# Thunder-Refix.net
KiCad netlist of a schematic drawn in Altium Designer
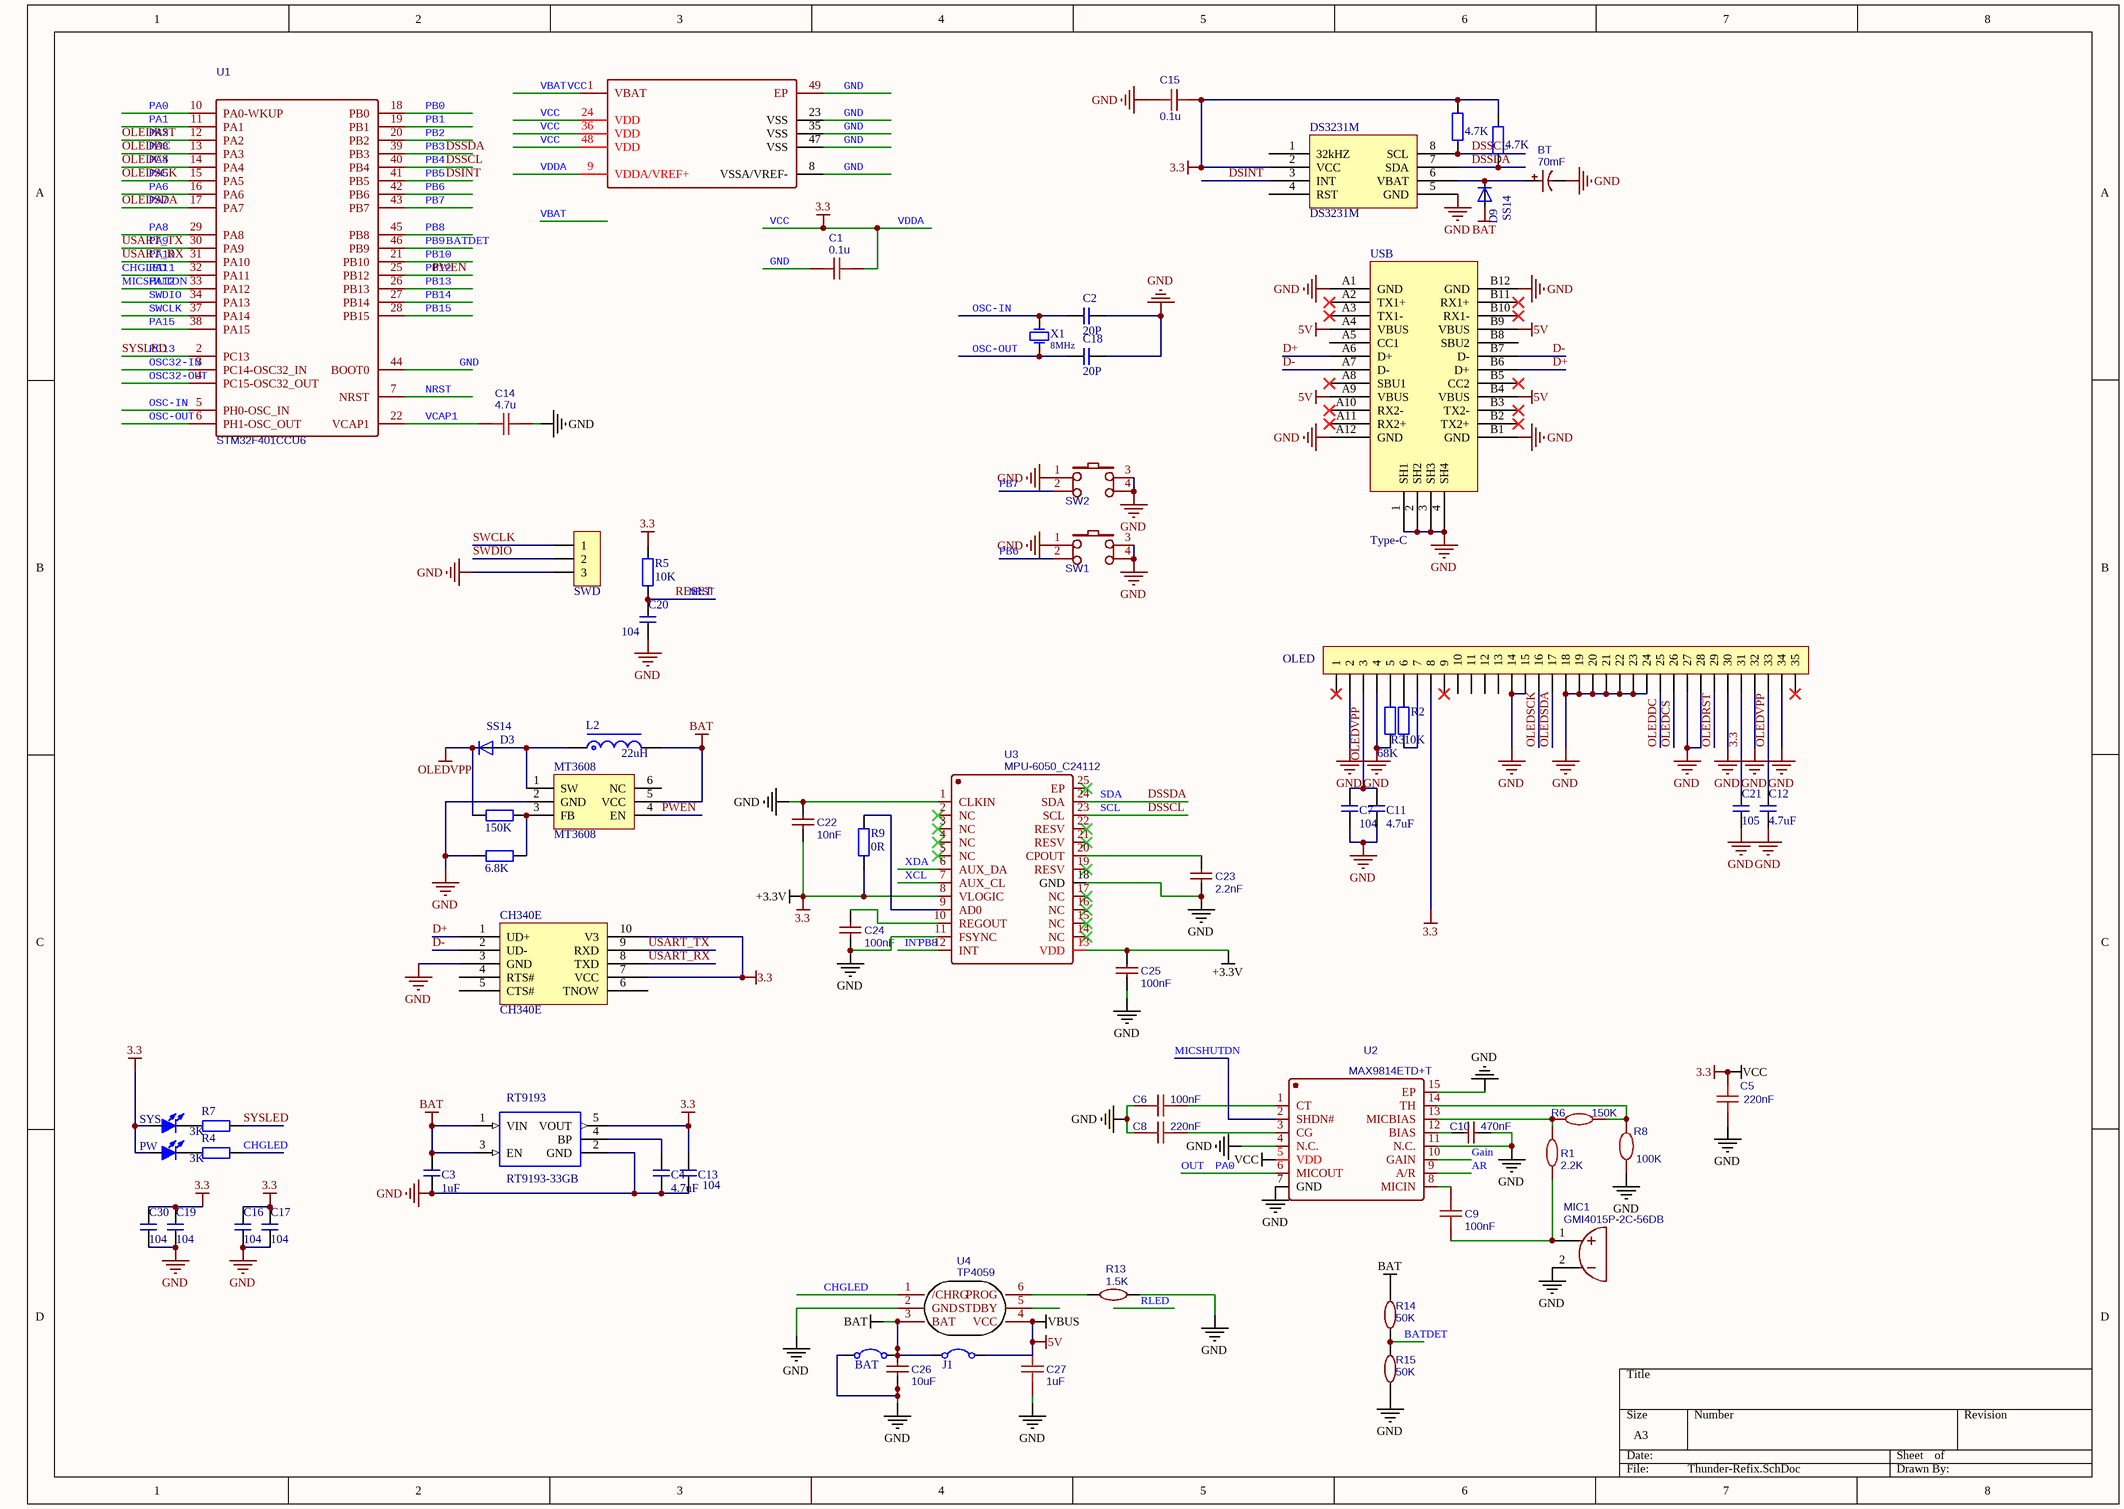
[diagram p0: Thunder-Refix.SchDoc]

(export (version "E")
  (design (tool "Eeschema 10.0.6"))
  (components
    (comp (ref "BAT")
      (value "Jump")
      (footprint "jump1")
      (description "跳线")
      (fields (field (name "版权归属") "源创客"))
      (libsource (lib "3.2   - 跳线") (part "Jump"))
    )
    (comp (ref "BT")
      (value "70mF")
      (footprint "MS621FE-FL11E")
      (fields
        (field (name "BOM_SUPPLIER PART") "C132600")
        (field (name "BOM_MANUFACTURER PART") "SM3R3703T01")
        (field (name "CONTRIBUTOR") "LCSC")
      )
      (libsource (lib "altium-import") (part "root_0_70mF_"))
    )
    (comp (ref "C1")
      (value "0.1u")
      (footprint "0603C")
      (fields (field (name "CONTRIBUTOR") "LCEDA_Lib"))
      (libsource (lib "altium-import") (part "root_2_0.1u_"))
    )
    (comp (ref "C2") (value "20P") (footprint "0603C") (libsource (lib "Schlib1") (part "电容")))
    (comp (ref "C3") (value "1uF") (footprint "0603C") (libsource (lib "Schlib1") (part "电容")))
    (comp (ref "C4") (value "4.7uF") (footprint "0603C") (libsource (lib "Schlib1") (part "电容")))
    (comp (ref "C5")
      (value "220nF")
      (footprint "0603c")
      (fields
        (field (name "BOM_SUPPLIER PART") "C354366")
        (field (name "BOM_MANUFACTURER PART") "GCJ21BR71H224KA01L")
        (field (name "CONTRIBUTOR") "LCSC")
      )
      (libsource (lib "altium-import") (part "root_1_220nF_"))
    )
    (comp (ref "C6")
      (value "100nF")
      (footprint "0603c")
      (fields
        (field (name "BOM_SUPPLIER PART") "C444732")
        (field (name "BOM_MANUFACTURER PART") "FS055C104K4Z2A")
        (field (name "CONTRIBUTOR") "LCSC")
      )
      (libsource (lib "") (part "root_1_100nF__1"))
    )
    (comp (ref "C7") (value "104") (footprint "0603C") (libsource (lib "Schlib1") (part "电容")))
    (comp (ref "C8")
      (value "220nF")
      (footprint "0603c")
      (fields
        (field (name "BOM_SUPPLIER PART") "C354366")
        (field (name "BOM_MANUFACTURER PART") "GCJ21BR71H224KA01L")
        (field (name "CONTRIBUTOR") "LCSC")
      )
      (libsource (lib "altium-import") (part "root_0_220nF_"))
    )
    (comp (ref "C9")
      (value "100nF")
      (footprint "0603c")
      (fields
        (field (name "BOM_SUPPLIER PART") "C444732")
        (field (name "BOM_MANUFACTURER PART") "FS055C104K4Z2A")
        (field (name "CONTRIBUTOR") "LCSC")
      )
      (libsource (lib "altium-import") (part "root_0_100nF_"))
    )
    (comp (ref "C10")
      (value "470nF")
      (footprint "0603c")
      (fields
        (field (name "BOM_MANUFACTURER PART") "CL21B474KBFNNNE")
        (field (name "BOM_SUPPLIER PART") "C13967")
      )
      (libsource (lib "altium-import") (part "root_0_470nF_"))
    )
    (comp (ref "C11") (value "4.7uF") (footprint "0603C") (libsource (lib "Schlib1") (part "电容")))
    (comp (ref "C12") (value "4.7uF") (footprint "0603C") (libsource (lib "Schlib1") (part "电容")))
    (comp (ref "C13") (value "104") (footprint "0603C") (libsource (lib "Schlib1") (part "电容")))
    (comp (ref "C14")
      (value "4.7u")
      (footprint "0603C")
      (fields (field (name "CONTRIBUTOR") "LCEDA_Lib"))
      (libsource (lib "altium-import") (part "root_0_4.7u_"))
    )
    (comp (ref "C15")
      (value "0.1u")
      (footprint "0603C")
      (fields (field (name "CONTRIBUTOR") "LCEDA_Lib"))
      (libsource (lib "altium-import") (part "root_2_0.1u_"))
    )
    (comp (ref "C16") (value "104") (footprint "0603C") (libsource (lib "Schlib1") (part "电容")))
    (comp (ref "C17") (value "104") (footprint "0603C") (libsource (lib "Schlib1") (part "电容")))
    (comp (ref "C18") (value "20P") (footprint "0603C") (libsource (lib "Schlib1") (part "电容")))
    (comp (ref "C19") (value "104") (footprint "0603C") (libsource (lib "Schlib1") (part "电容")))
    (comp (ref "C20") (value "104") (footprint "0603C") (libsource (lib "Schlib1") (part "电容")))
    (comp (ref "C21") (value "105") (footprint "0603C") (libsource (lib "Schlib1") (part "电容")))
    (comp (ref "C22")
      (value "10nF")
      (footprint "0603C")
      (fields
        (field (name "BOM_MANUFACTURER PART") "0603B103K500NT")
        (field (name "BOM_SUPPLIER PART") "C57112")
      )
      (libsource (lib "altium-import") (part "root_1_10nF_"))
    )
    (comp (ref "C23")
      (value "2.2nF")
      (footprint "0603C")
      (fields
        (field (name "BOM_MANUFACTURER PART") "0603B222K500NT")
        (field (name "BOM_SUPPLIER PART") "C1604")
      )
      (libsource (lib "altium-import") (part "root_1_2.2nF_"))
    )
    (comp (ref "C24")
      (value "100nF")
      (footprint "0603C")
      (fields
        (field (name "BOM_MANUFACTURER PART") "CL05B104KO5NNNC")
        (field (name "BOM_SUPPLIER PART") "C1525")
      )
      (libsource (lib "altium-import") (part "root_1_100nF_"))
    )
    (comp (ref "C25")
      (value "100nF")
      (footprint "0603C")
      (fields
        (field (name "BOM_MANUFACTURER PART") "CL05B104KO5NNNC")
        (field (name "BOM_SUPPLIER PART") "C1525")
      )
      (libsource (lib "altium-import") (part "root_1_100nF_"))
    )
    (comp (ref "C26")
      (value "10uF")
      (footprint "0603c")
      (fields
        (field (name "BOM_SUPPLIER PART") "C162317")
        (field (name "BOM_MANUFACTURER PART") "GRM21BB31C106KE15L")
        (field (name "CONTRIBUTOR") "LCSC")
      )
      (libsource (lib "altium-import") (part "root_1_10uF_"))
    )
    (comp (ref "C27")
      (value "1uF")
      (footprint "0603c")
      (fields
        (field (name "BOM_SUPPLIER PART") "C319195")
        (field (name "BOM_MANUFACTURER PART") "UMK212BJ105KG-T")
        (field (name "CONTRIBUTOR") "LCSC")
      )
      (libsource (lib "altium-import") (part "root_1_1uF_"))
    )
    (comp (ref "C30") (value "104") (footprint "0603C") (libsource (lib "Schlib1") (part "电容")))
    (comp (ref "CH340E") (value "CH340E") (footprint "MSOP10_L") (libsource (lib "CUBE_T1") (part "CH340E")))
    (comp (ref "D3")
      (value "SS14")
      (footprint "SOD323_1N4148WS")
      (description "Diode Switching 75V 0.3A 2-Pin SOD-323 T/R")
      (fields (field (name "MF") "ON Semiconductor") (field (name "MP") "1N4148WS"))
      (libsource (lib "1N4148WS") (part "1N4148WS"))
    )
    (comp (ref "D9")
      (value "SS14")
      (footprint "SOD323_1N4148WS")
      (description "Diode Switching 75V 0.3A 2-Pin SOD-323 T/R")
      (fields (field (name "MF") "ON Semiconductor") (field (name "MP") "1N4148WS"))
      (libsource (lib "1N4148WS") (part "1N4148WS"))
    )
    (comp (ref "DS3231M") (value "DS3231M") (footprint "SOP8") (libsource (lib "CUBE_T1") (part "DS3231M")))
    (comp (ref "J1")
      (value "Jump")
      (footprint "jump1")
      (description "跳线")
      (fields (field (name "版权归属") "源创客"))
      (libsource (lib "3.2   - 跳线") (part "Jump"))
    )
    (comp (ref "L2")
      (value "22uH")
      (footprint "1210-ec")
      (description "功率屏蔽电感")
      (fields (field (name "版权归属") "源创客"))
      (libsource (lib "3.1   - 电阻-电容-电感") (part "L-CDRH"))
    )
    (comp (ref "MIC1")
      (value "GMI4015P-2C-56DB")
      (footprint "MIC-TH_BD4.0-P2.00-D0.4-L-FD")
      (fields
        (field (name "BOM_SUPPLIER PART") "C233299")
        (field (name "BOM_MANUFACTURER PART") "GMI4015P-2C-56db")
        (field (name "CONTRIBUTOR") "LCSC")
      )
      (libsource (lib "altium-import") (part "root_0_GMI4015P-2C-56DB_"))
    )
    (comp (ref "MT3608")
      (value "MT3608")
      (footprint "SOT23-6N")
      (description "可调升压芯片")
      (fields (field (name "版权归属") "源创客"))
      (libsource (lib "1.3   - 电源类芯片") (part "SX1308"))
    )
    (comp (ref "OLED")
      (value "FPC1.0-35P")
      (footprint "1.69 OLED")
      (description "FPC连接器")
      (fields (field (name "版权归属") "源创客"))
      (libsource (lib "4.14 - FPC连接器") (part "FPC-35P"))
    )
    (comp (ref "PW")
      (value "白色")
      (footprint "0603LED")
      (description "方形LED")
      (fields (field (name "版权归属") "源创客"))
      (libsource (lib "9.1   - LED") (part "LED-F234"))
    )
    (comp (ref "R1")
      (value "2.2K")
      (footprint "0603r")
      (fields
        (field (name "BOM_SUPPLIER PART") "C325769")
        (field (name "BOM_MANUFACTURER PART") "RMC08052.2K1%N")
        (field (name "CONTRIBUTOR") "LCSC")
      )
      (libsource (lib "altium-import") (part "root_1_2.2K_"))
    )
    (comp (ref "R2")
      (value "10K")
      (footprint "0603R")
      (description "贴片电阻")
      (fields (field (name "版权归属") "源创客"))
      (libsource (lib "3.1   - 电阻-电容-电感") (part "R"))
    )
    (comp (ref "R3")
      (value "68K")
      (footprint "0603R")
      (description "贴片电阻")
      (fields (field (name "版权归属") "源创客"))
      (libsource (lib "3.1   - 电阻-电容-电感") (part "R"))
    )
    (comp (ref "R4")
      (value "3K")
      (footprint "0603R")
      (description "贴片电阻")
      (fields (field (name "版权归属") "源创客"))
      (libsource (lib "3.1   - 电阻-电容-电感") (part "R"))
    )
    (comp (ref "R5")
      (value "10K")
      (footprint "0603R")
      (description "贴片电阻")
      (fields (field (name "版权归属") "源创客"))
      (libsource (lib "3.1   - 电阻-电容-电感") (part "R"))
    )
    (comp (ref "R6")
      (value "150K")
      (footprint "0603r")
      (fields
        (field (name "BOM_SUPPLIER PART") "C325765")
        (field (name "BOM_MANUFACTURER PART") "RMC0805150K1%N")
        (field (name "CONTRIBUTOR") "LCSC")
      )
      (libsource (lib "altium-import") (part "root_0_150K_"))
    )
    (comp (ref "R7")
      (value "3K")
      (footprint "0603R")
      (description "贴片电阻")
      (fields (field (name "版权归属") "源创客"))
      (libsource (lib "3.1   - 电阻-电容-电感") (part "R"))
    )
    (comp (ref "R8")
      (value "100K")
      (footprint "0603r")
      (fields
        (field (name "BOM_SUPPLIER PART") "C346756")
        (field (name "BOM_MANUFACTURER PART") "RTAN0805BKE100K")
        (field (name "CONTRIBUTOR") "LCSC")
      )
      (libsource (lib "altium-import") (part "root_1_100K_"))
    )
    (comp (ref "R9")
      (value "0R")
      (footprint "0603R")
      (description "贴片电阻")
      (fields (field (name "版权归属") "源创客"))
      (libsource (lib "3.1   - 电阻-电容-电感") (part "R"))
    )
    (comp (ref "R10")
      (value "4.7K")
      (footprint "0603R")
      (description "贴片电阻")
      (fields (field (name "版权归属") "源创客"))
      (libsource (lib "3.1   - 电阻-电容-电感") (part "R"))
    )
    (comp (ref "R11")
      (value "4.7K")
      (footprint "0603R")
      (description "贴片电阻")
      (fields (field (name "版权归属") "源创客"))
      (libsource (lib "3.1   - 电阻-电容-电感") (part "R"))
    )
    (comp (ref "R13")
      (value "1.5K")
      (footprint "0603r")
      (fields
        (field (name "BOM_MANUFACTURER PART") "RC0603FR-071K5L")
        (field (name "BOM_SUPPLIER PART") "C114668")
      )
      (libsource (lib "altium-import") (part "root_0_1.5K_"))
    )
    (comp (ref "R14")
      (value "50K")
      (footprint "0603r")
      (fields
        (field (name "BOM_MANUFACTURER PART") "RC0603FR-071K5L")
        (field (name "BOM_SUPPLIER PART") "C114668")
      )
      (libsource (lib "altium-import") (part "root_1_1.5K_"))
    )
    (comp (ref "R15")
      (value "50K")
      (footprint "0603r")
      (fields
        (field (name "BOM_MANUFACTURER PART") "RC0603FR-071K5L")
        (field (name "BOM_SUPPLIER PART") "C114668")
      )
      (libsource (lib "altium-import") (part "root_1_1.5K_"))
    )
    (comp (ref "RB")
      (value "150K")
      (footprint "0603R")
      (description "贴片电阻")
      (fields (field (name "版权归属") "源创客"))
      (libsource (lib "3.1   - 电阻-电容-电感") (part "R"))
    )
    (comp (ref "RS")
      (value "6.8K")
      (footprint "0603R")
      (description "贴片电阻")
      (fields (field (name "版权归属") "源创客"))
      (libsource (lib "3.1   - 电阻-电容-电感") (part "R"))
    )
    (comp (ref "RT9193")
      (value "RT9193-33GB")
      (footprint "sot23-5")
      (description "RT9193 Series 300 mA 3.3 V Ultra-Low Noise Ultra-Fast CMOS LDO Regulator-SC-70-5")
      (fields (field (name "MF") "Richtek USA"))
      (libsource (lib "RT9193-33GB") (part "RT9193-33GB"))
    )
    (comp (ref "SW1")
      (value "Button-SMD-4x4x1.5")
      (footprint "SW-SMD_TS-1086E-16")
      (fields
        (field (name "BOM_SUPPLIER PART") "C71830")
        (field (name "BOM_MANUFACTURER PART") "4*4*1.5Copper head,260G, 0.25mm,")
      )
      (libsource (lib "altium-import") (part "root_0_Button-SMD-4x4x1.5_"))
    )
    (comp (ref "SW2")
      (value "Button-SMD-4x4x1.5")
      (footprint "SW-SMD_TS-1086E-16")
      (fields
        (field (name "BOM_SUPPLIER PART") "C71830")
        (field (name "BOM_MANUFACTURER PART") "4*4*1.5Copper head,260G, 0.25mm,")
      )
      (libsource (lib "altium-import") (part "root_0_Button-SMD-4x4x1.5_"))
    )
    (comp (ref "SWD")
      (value "HDR-1X3")
      (footprint "ZH1.5-LI-3P")
      (description "3P接插件")
      (fields (field (name "版权归属") "源创客"))
      (libsource (lib "4.3   - 接插件-脚距1.5") (part "Header 3"))
    )
    (comp (ref "SYS")
      (value "粉色")
      (footprint "0603LED")
      (description "方形LED")
      (fields (field (name "版权归属") "源创客"))
      (libsource (lib "9.1   - LED") (part "LED-F234"))
    )
    (comp (ref "U1")
      (value "STM32F401CCU6")
      (footprint "QFN48 7X7_N")
      (fields (field (name "BOM_SUPPLIER PART") "C79861") (field (name "SUBPART_NO") "1"))
      (libsource (lib "Galaxy") (part "STM32F401CCU6"))
    )
    (comp (ref "U2")
      (value "MAX9814ETD+T")
      (footprint "TDFN-14_L3.0-W3.0-P0.40-BL-EP")
      (fields (field (name "BOM_SUPPLIER PART") "C41714"))
      (libsource (lib "altium-import") (part "root_0_MAX9814ETD+T_"))
    )
    (comp (ref "U3")
      (value "MPU-6050_C24112")
      (footprint "QFN24 4x4_N")
      (fields (field (name "BOM_MANUFACTURER PART") "MPU-6050") (field (name "BOM_SUPPLIER PART") "C24112"))
      (libsource (lib "altium-import") (part "root_0_MPU-6050_C24112_"))
    )
    (comp (ref "U4")
      (value "TP4059")
      (footprint "SOT23-6N")
      (fields (field (name "BOM_SUPPLIER PART") "C80364"))
      (libsource (lib "altium-import") (part "root_0_TP4059_"))
    )
    (comp (ref "USB") (value "Type-C") (footprint "Type-C") (libsource (lib "元件") (part "Type-C")))
    (comp (ref "X1")
      (value "8MHz")
      (footprint "OSC 5032-2P")
      (description "XTAL,8MHz,±20PPM,12.6*4.5")
      (fields (field (name "Comment") "1.6.1.01.005.001"))
      (libsource (lib "Mark_7") (part "1.6.1.01.005.001"))
    )
  )
  (nets
    (net (code "1") (name "+3.3V") (class "Default")
      (node (ref "C1") (pin "1") (pinfunction "1_1") (pintype "passive"))
      (node (ref "C13") (pin "2") (pinfunction "2_2") (pintype "passive"))
      (node (ref "C15") (pin "1") (pinfunction "1_1") (pintype "passive"))
      (node (ref "C16") (pin "1") (pinfunction "1_1") (pintype "passive"))
      (node (ref "C17") (pin "1") (pinfunction "1_1") (pintype "passive"))
      (node (ref "C19") (pin "1") (pinfunction "1_1") (pintype "passive"))
      (node (ref "C21") (pin "1") (pinfunction "1_1") (pintype "passive"))
      (node (ref "C22") (pin "1") (pinfunction "1_1") (pintype "passive"))
      (node (ref "C25") (pin "2") (pinfunction "2_2") (pintype "passive"))
      (node (ref "C30") (pin "1") (pinfunction "1_1") (pintype "passive"))
      (node (ref "C5") (pin "2") (pinfunction "2_2") (pintype "passive"))
      (node (ref "CH340E") (pin "10") (pinfunction "V3_10") (pintype "passive"))
      (node (ref "CH340E") (pin "7") (pinfunction "VCC_7") (pintype "passive"))
      (node (ref "DS3231M") (pin "2") (pinfunction "VCC_2") (pintype "passive"))
      (node (ref "OLED") (pin "31") (pinfunction "31_31") (pintype "passive"))
      (node (ref "OLED") (pin "8") (pinfunction "8_8") (pintype "passive"))
      (node (ref "PW") (pin "1") (pinfunction "A_1") (pintype "passive"))
      (node (ref "R10") (pin "1") (pinfunction "1_1") (pintype "passive"))
      (node (ref "R11") (pin "1") (pinfunction "1_1") (pintype "passive"))
      (node (ref "R5") (pin "1") (pinfunction "1_1") (pintype "passive"))
      (node (ref "R9") (pin "1") (pinfunction "1_1") (pintype "passive"))
      (node (ref "RT9193") (pin "5") (pinfunction "VOUT_5") (pintype "output"))
      (node (ref "SYS") (pin "1") (pinfunction "A_1") (pintype "passive"))
      (node (ref "U1") (pin "1") (pinfunction "VBAT_1") (pintype "passive"))
      (node (ref "U1") (pin "24") (pinfunction "VDD_24") (pintype "passive"))
      (node (ref "U1") (pin "36") (pinfunction "VDD_36") (pintype "passive"))
      (node (ref "U1") (pin "48") (pinfunction "VDD_48") (pintype "passive"))
      (node (ref "U1") (pin "9") (pinfunction "VDDA/VREF+_9") (pintype "passive"))
      (node (ref "U2") (pin "5") (pinfunction "VDD_5") (pintype "passive"))
      (node (ref "U3") (pin "13") (pinfunction "VDD_13") (pintype "passive"))
      (node (ref "U3") (pin "8") (pinfunction "VLOGIC_8") (pintype "passive"))
    )
    (net (code "2") (name "/AR") (class "Default")
      (node (ref "U2") (pin "9") (pinfunction "A/R_9") (pintype "passive"))
    )
    (net (code "3") (name "/BATDET") (class "Default")
      (node (ref "R14") (pin "1") (pinfunction "1_1") (pintype "passive"))
      (node (ref "R15") (pin "2") (pinfunction "2_2") (pintype "passive"))
      (node (ref "U1") (pin "46") (pinfunction "PB9_46") (pintype "passive"))
    )
    (net (code "4") (name "/CHGLED") (class "Default")
      (node (ref "R4") (pin "1") (pinfunction "1_1") (pintype "passive"))
      (node (ref "U1") (pin "32") (pinfunction "PA11_32") (pintype "passive"))
      (node (ref "U4") (pin "1") (pinfunction "/CHRG_1") (pintype "passive"))
    )
    (net (code "5") (name "/D+") (class "Default")
      (node (ref "CH340E") (pin "1") (pinfunction "UD+_1") (pintype "passive"))
      (node (ref "USB") (pin "A6") (pinfunction "D+_A6") (pintype "passive"))
      (node (ref "USB") (pin "B6") (pinfunction "D+_B6") (pintype "passive"))
    )
    (net (code "6") (name "/D-") (class "Default")
      (node (ref "CH340E") (pin "2") (pinfunction "UD-_2") (pintype "passive"))
      (node (ref "USB") (pin "A7") (pinfunction "D-_A7") (pintype "passive"))
      (node (ref "USB") (pin "B7") (pinfunction "D-_B7") (pintype "passive"))
    )
    (net (code "7") (name "/DSINT") (class "Default")
      (node (ref "DS3231M") (pin "3") (pinfunction "INT_3") (pintype "passive"))
      (node (ref "U1") (pin "41") (pinfunction "PB5_41") (pintype "passive"))
    )
    (net (code "8") (name "/DSSCL") (class "Default")
      (node (ref "DS3231M") (pin "8") (pinfunction "SCL_8") (pintype "passive"))
      (node (ref "R10") (pin "2") (pinfunction "2_2") (pintype "passive"))
      (node (ref "U1") (pin "40") (pinfunction "PB4_40") (pintype "passive"))
      (node (ref "U3") (pin "23") (pinfunction "SCL_23") (pintype "passive"))
    )
    (net (code "9") (name "/DSSDA") (class "Default")
      (node (ref "DS3231M") (pin "7") (pinfunction "SDA_7") (pintype "passive"))
      (node (ref "R11") (pin "2") (pinfunction "2_2") (pintype "passive"))
      (node (ref "U1") (pin "39") (pinfunction "PB3_39") (pintype "passive"))
      (node (ref "U3") (pin "24") (pinfunction "SDA_24") (pintype "passive"))
    )
    (net (code "10") (name "/Gain") (class "Default")
      (node (ref "U2") (pin "10") (pinfunction "GAIN_10") (pintype "passive"))
    )
    (net (code "11") (name "/INT") (class "Default")
      (node (ref "U1") (pin "45") (pinfunction "PB8_45") (pintype "passive"))
      (node (ref "U3") (pin "12") (pinfunction "INT_12") (pintype "passive"))
    )
    (net (code "12") (name "/MICSHUTDN") (class "Default")
      (node (ref "U1") (pin "33") (pinfunction "PA12_33") (pintype "passive"))
      (node (ref "U2") (pin "2") (pinfunction "SHDN#_2") (pintype "passive"))
    )
    (net (code "13") (name "/NRST") (class "Default")
      (node (ref "C20") (pin "1") (pinfunction "1_1") (pintype "passive"))
      (node (ref "R5") (pin "2") (pinfunction "2_2") (pintype "passive"))
      (node (ref "U1") (pin "7") (pinfunction "NRST_7") (pintype "passive"))
    )
    (net (code "14") (name "/OLEDCS") (class "Default")
      (node (ref "OLED") (pin "26") (pinfunction "26_26") (pintype "passive"))
      (node (ref "U1") (pin "14") (pinfunction "PA4_14") (pintype "passive"))
    )
    (net (code "15") (name "/OLEDDC") (class "Default")
      (node (ref "OLED") (pin "25") (pinfunction "25_25") (pintype "passive"))
      (node (ref "U1") (pin "13") (pinfunction "PA3_13") (pintype "passive"))
    )
    (net (code "16") (name "/OLEDRST") (class "Default")
      (node (ref "OLED") (pin "29") (pinfunction "29_29") (pintype "passive"))
      (node (ref "U1") (pin "12") (pinfunction "PA2_12") (pintype "passive"))
    )
    (net (code "17") (name "/OLEDSCK") (class "Default")
      (node (ref "OLED") (pin "16") (pinfunction "16_16") (pintype "passive"))
      (node (ref "U1") (pin "15") (pinfunction "PA5_15") (pintype "passive"))
    )
    (net (code "18") (name "/OLEDSDA") (class "Default")
      (node (ref "OLED") (pin "17") (pinfunction "17_17") (pintype "passive"))
      (node (ref "U1") (pin "17") (pinfunction "PA7_17") (pintype "passive"))
    )
    (net (code "19") (name "/OSC-IN") (class "Default")
      (node (ref "C2") (pin "2") (pinfunction "2_2") (pintype "passive"))
      (node (ref "U1") (pin "5") (pinfunction "PH0-OSC_IN_5") (pintype "passive"))
      (node (ref "X1") (pin "1") (pinfunction "OSC1_1") (pintype "passive"))
    )
    (net (code "20") (name "/OSC-OUT") (class "Default")
      (node (ref "C18") (pin "2") (pinfunction "2_2") (pintype "passive"))
      (node (ref "U1") (pin "6") (pinfunction "PH1-OSC_OUT_6") (pintype "passive"))
      (node (ref "X1") (pin "2") (pinfunction "OSC2_2") (pintype "passive"))
    )
    (net (code "21") (name "/OSC32-IN") (class "Default")
      (node (ref "U1") (pin "3") (pinfunction "PC14-OSC32_IN_3") (pintype "passive"))
    )
    (net (code "22") (name "/OSC32-OUT") (class "Default")
      (node (ref "U1") (pin "4") (pinfunction "PC15-OSC32_OUT_4") (pintype "passive"))
    )
    (net (code "23") (name "/OUT") (class "Default")
      (node (ref "U1") (pin "10") (pinfunction "PA0-WKUP_10") (pintype "passive"))
      (node (ref "U2") (pin "6") (pinfunction "MICOUT_6") (pintype "passive"))
    )
    (net (code "24") (name "/PA1") (class "Default")
      (node (ref "U1") (pin "11") (pinfunction "PA1_11") (pintype "passive"))
    )
    (net (code "25") (name "/PA6") (class "Default")
      (node (ref "U1") (pin "16") (pinfunction "PA6_16") (pintype "passive"))
    )
    (net (code "26") (name "/PA8") (class "Default")
      (node (ref "U1") (pin "29") (pinfunction "PA8_29") (pintype "passive"))
    )
    (net (code "27") (name "/PA9") (class "Default")
      (node (ref "CH340E") (pin "9") (pinfunction "RXD_9") (pintype "passive"))
      (node (ref "U1") (pin "30") (pinfunction "PA9_30") (pintype "passive"))
    )
    (net (code "28") (name "/PA10") (class "Default")
      (node (ref "CH340E") (pin "8") (pinfunction "TXD_8") (pintype "passive"))
      (node (ref "U1") (pin "31") (pinfunction "PA10_31") (pintype "passive"))
    )
    (net (code "29") (name "/PA15") (class "Default")
      (node (ref "U1") (pin "38") (pinfunction "PA15_38") (pintype "passive"))
    )
    (net (code "30") (name "/PB0") (class "Default")
      (node (ref "U1") (pin "18") (pinfunction "PB0_18") (pintype "passive"))
    )
    (net (code "31") (name "/PB1") (class "Default")
      (node (ref "U1") (pin "19") (pinfunction "PB1_19") (pintype "passive"))
    )
    (net (code "32") (name "/PB2") (class "Default")
      (node (ref "U1") (pin "20") (pinfunction "PB2_20") (pintype "passive"))
    )
    (net (code "33") (name "/PB6") (class "Default")
      (node (ref "SW1") (pin "2") (pinfunction "2_2") (pintype "passive"))
      (node (ref "U1") (pin "42") (pinfunction "PB6_42") (pintype "passive"))
    )
    (net (code "34") (name "/PB7") (class "Default")
      (node (ref "SW2") (pin "2") (pinfunction "2_2") (pintype "passive"))
      (node (ref "U1") (pin "43") (pinfunction "PB7_43") (pintype "passive"))
    )
    (net (code "35") (name "/PB10") (class "Default")
      (node (ref "U1") (pin "21") (pinfunction "PB10_21") (pintype "passive"))
    )
    (net (code "36") (name "/PB12") (class "Default")
      (node (ref "MT3608") (pin "4") (pinfunction "EN_4") (pintype "passive"))
      (node (ref "U1") (pin "25") (pinfunction "PB12_25") (pintype "passive"))
    )
    (net (code "37") (name "/PB13") (class "Default")
      (node (ref "U1") (pin "26") (pinfunction "PB13_26") (pintype "passive"))
    )
    (net (code "38") (name "/PB14") (class "Default")
      (node (ref "U1") (pin "27") (pinfunction "PB14_27") (pintype "passive"))
    )
    (net (code "39") (name "/PB15") (class "Default")
      (node (ref "U1") (pin "28") (pinfunction "PB15_28") (pintype "passive"))
    )
    (net (code "40") (name "/PC13") (class "Default")
      (node (ref "R7") (pin "1") (pinfunction "1_1") (pintype "passive"))
      (node (ref "U1") (pin "2") (pinfunction "PC13_2") (pintype "passive"))
    )
    (net (code "42") (name "/SWCLK") (class "Default")
      (node (ref "SWD") (pin "1") (pinfunction "1_1") (pintype "passive"))
      (node (ref "U1") (pin "37") (pinfunction "PA14_37") (pintype "passive"))
    )
    (net (code "43") (name "/SWDIO") (class "Default")
      (node (ref "SWD") (pin "2") (pinfunction "2_2") (pintype "passive"))
      (node (ref "U1") (pin "34") (pinfunction "PA13_34") (pintype "passive"))
    )
    (net (code "44") (name "/VCAP1") (class "Default")
      (node (ref "C14") (pin "1") (pinfunction "1_1") (pintype "passive"))
      (node (ref "U1") (pin "22") (pinfunction "VCAP1_22") (pintype "passive"))
    )
    (net (code "45") (name "/XCL") (class "Default")
      (node (ref "U3") (pin "7") (pinfunction "AUX_CL_7") (pintype "passive"))
    )
    (net (code "46") (name "/XDA") (class "Default")
      (node (ref "U3") (pin "6") (pinfunction "AUX_DA_6") (pintype "passive"))
    )
    (net (code "47") (name "5V") (class "Default")
      (node (ref "C27") (pin "1") (pinfunction "1_1") (pintype "passive"))
      (node (ref "J1") (pin "2") (pinfunction "2_2") (pintype "passive"))
      (node (ref "U4") (pin "4") (pinfunction "VCC_4") (pintype "passive"))
      (node (ref "USB") (pin "A4") (pinfunction "VBUS_A4") (pintype "passive"))
      (node (ref "USB") (pin "A9") (pinfunction "VBUS_A9") (pintype "passive"))
      (node (ref "USB") (pin "B4") (pinfunction "VBUS_B4") (pintype "passive"))
      (node (ref "USB") (pin "B9") (pinfunction "VBUS_B9") (pintype "passive"))
    )
    (net (code "48") (name "BAT") (class "Default")
      (node (ref "BAT") (pin "2") (pinfunction "2_2") (pintype "passive"))
      (node (ref "C26") (pin "2") (pinfunction "2_2") (pintype "passive"))
      (node (ref "C3") (pin "2") (pinfunction "2_2") (pintype "passive"))
      (node (ref "D9") (pin "A") (pinfunction "A_A") (pintype "passive"))
      (node (ref "J1") (pin "1") (pinfunction "1_1") (pintype "passive"))
      (node (ref "L2") (pin "2") (pinfunction "2_2") (pintype "passive"))
      (node (ref "MT3608") (pin "5") (pinfunction "VCC_5") (pintype "passive"))
      (node (ref "R14") (pin "2") (pinfunction "2_2") (pintype "passive"))
      (node (ref "RT9193") (pin "1") (pinfunction "VIN_1") (pintype "input"))
      (node (ref "RT9193") (pin "3") (pinfunction "EN_3") (pintype "input"))
      (node (ref "U4") (pin "3") (pinfunction "BAT_3") (pintype "passive"))
    )
    (net (code "49") (name "GND") (class "Default")
      (node (ref "BAT") (pin "1") (pinfunction "1_1") (pintype "passive"))
      (node (ref "BT") (pin "2") (pinfunction "2_2") (pintype "passive"))
      (node (ref "C1") (pin "2") (pinfunction "2_2") (pintype "passive"))
      (node (ref "C10") (pin "2") (pinfunction "2_2") (pintype "passive"))
      (node (ref "C11") (pin "2") (pinfunction "2_2") (pintype "passive"))
      (node (ref "C12") (pin "2") (pinfunction "2_2") (pintype "passive"))
      (node (ref "C13") (pin "1") (pinfunction "1_1") (pintype "passive"))
      (node (ref "C14") (pin "2") (pinfunction "2_2") (pintype "passive"))
      (node (ref "C15") (pin "2") (pinfunction "2_2") (pintype "passive"))
      (node (ref "C16") (pin "2") (pinfunction "2_2") (pintype "passive"))
      (node (ref "C17") (pin "2") (pinfunction "2_2") (pintype "passive"))
      (node (ref "C18") (pin "1") (pinfunction "1_1") (pintype "passive"))
      (node (ref "C19") (pin "2") (pinfunction "2_2") (pintype "passive"))
      (node (ref "C2") (pin "1") (pinfunction "1_1") (pintype "passive"))
      (node (ref "C20") (pin "2") (pinfunction "2_2") (pintype "passive"))
      (node (ref "C21") (pin "2") (pinfunction "2_2") (pintype "passive"))
      (node (ref "C22") (pin "2") (pinfunction "2_2") (pintype "passive"))
      (node (ref "C23") (pin "1") (pinfunction "1_1") (pintype "passive"))
      (node (ref "C24") (pin "1") (pinfunction "1_1") (pintype "passive"))
      (node (ref "C25") (pin "1") (pinfunction "1_1") (pintype "passive"))
      (node (ref "C26") (pin "1") (pinfunction "1_1") (pintype "passive"))
      (node (ref "C27") (pin "2") (pinfunction "2_2") (pintype "passive"))
      (node (ref "C3") (pin "1") (pinfunction "1_1") (pintype "passive"))
      (node (ref "C30") (pin "2") (pinfunction "2_2") (pintype "passive"))
      (node (ref "C4") (pin "1") (pinfunction "1_1") (pintype "passive"))
      (node (ref "C5") (pin "1") (pinfunction "1_1") (pintype "passive"))
      (node (ref "C6") (pin "1") (pinfunction "1_1") (pintype "passive"))
      (node (ref "C7") (pin "2") (pinfunction "2_2") (pintype "passive"))
      (node (ref "C8") (pin "1") (pinfunction "1_1") (pintype "passive"))
      (node (ref "CH340E") (pin "3") (pinfunction "GND_3") (pintype "passive"))
      (node (ref "DS3231M") (pin "5") (pinfunction "GND_5") (pintype "passive"))
      (node (ref "MIC1") (pin "2") (pinfunction "2_2") (pintype "passive"))
      (node (ref "MT3608") (pin "2") (pinfunction "GND_2") (pintype "passive"))
      (node (ref "OLED") (pin "14") (pinfunction "14_14") (pintype "passive"))
      (node (ref "OLED") (pin "15") (pinfunction "15_15") (pintype "passive"))
      (node (ref "OLED") (pin "18") (pinfunction "18_18") (pintype "passive"))
      (node (ref "OLED") (pin "19") (pinfunction "19_19") (pintype "passive"))
      (node (ref "OLED") (pin "2") (pinfunction "2_2") (pintype "passive"))
      (node (ref "OLED") (pin "20") (pinfunction "20_20") (pintype "passive"))
      (node (ref "OLED") (pin "21") (pinfunction "21_21") (pintype "passive"))
      (node (ref "OLED") (pin "22") (pinfunction "22_22") (pintype "passive"))
      (node (ref "OLED") (pin "23") (pinfunction "23_23") (pintype "passive"))
      (node (ref "OLED") (pin "24") (pinfunction "24_24") (pintype "passive"))
      (node (ref "OLED") (pin "27") (pinfunction "27_27") (pintype "passive"))
      (node (ref "OLED") (pin "28") (pinfunction "28_28") (pintype "passive"))
      (node (ref "OLED") (pin "30") (pinfunction "30_30") (pintype "passive"))
      (node (ref "OLED") (pin "32") (pinfunction "32_32") (pintype "passive"))
      (node (ref "OLED") (pin "34") (pinfunction "34_34") (pintype "passive"))
      (node (ref "OLED") (pin "4") (pinfunction "4_4") (pintype "passive"))
      (node (ref "R13") (pin "2") (pinfunction "2_2") (pintype "passive"))
      (node (ref "R15") (pin "1") (pinfunction "1_1") (pintype "passive"))
      (node (ref "R3") (pin "1") (pinfunction "1_1") (pintype "passive"))
      (node (ref "R8") (pin "1") (pinfunction "1_1") (pintype "passive"))
      (node (ref "RS") (pin "1") (pinfunction "1_1") (pintype "passive"))
      (node (ref "RT9193") (pin "2") (pinfunction "GND_2") (pintype "power_in"))
      (node (ref "SW1") (pin "1") (pinfunction "1_1") (pintype "passive"))
      (node (ref "SW1") (pin "3") (pinfunction "3_3") (pintype "passive"))
      (node (ref "SW1") (pin "4") (pinfunction "4_4") (pintype "passive"))
      (node (ref "SW2") (pin "1") (pinfunction "1_1") (pintype "passive"))
      (node (ref "SW2") (pin "3") (pinfunction "3_3") (pintype "passive"))
      (node (ref "SW2") (pin "4") (pinfunction "4_4") (pintype "passive"))
      (node (ref "SWD") (pin "3") (pinfunction "3_3") (pintype "passive"))
      (node (ref "U1") (pin "23") (pinfunction "VSS_23") (pintype "passive"))
      (node (ref "U1") (pin "35") (pinfunction "VSS_35") (pintype "passive"))
      (node (ref "U1") (pin "44") (pinfunction "BOOT0_44") (pintype "passive"))
      (node (ref "U1") (pin "47") (pinfunction "VSS_47") (pintype "passive"))
      (node (ref "U1") (pin "49") (pinfunction "EP_49") (pintype "passive"))
      (node (ref "U1") (pin "8") (pinfunction "VSSA/VREF-_8") (pintype "passive"))
      (node (ref "U2") (pin "11") (pinfunction "N.C._11") (pintype "passive"))
      (node (ref "U2") (pin "15") (pinfunction "EP_15") (pintype "passive"))
      (node (ref "U2") (pin "4") (pinfunction "N.C._4") (pintype "passive"))
      (node (ref "U2") (pin "7") (pinfunction "GND_7") (pintype "passive"))
      (node (ref "U3") (pin "1") (pinfunction "CLKIN_1") (pintype "passive"))
      (node (ref "U3") (pin "11") (pinfunction "FSYNC_11") (pintype "passive"))
      (node (ref "U3") (pin "18") (pinfunction "GND_18") (pintype "passive"))
      (node (ref "U4") (pin "2") (pinfunction "GND_2") (pintype "passive"))
      (node (ref "USB") (pin "1") (pinfunction "SH1_1") (pintype "passive"))
      (node (ref "USB") (pin "2") (pinfunction "SH2_2") (pintype "passive"))
      (node (ref "USB") (pin "3") (pinfunction "SH3_3") (pintype "passive"))
      (node (ref "USB") (pin "4") (pinfunction "SH4_4") (pintype "passive"))
      (node (ref "USB") (pin "A1") (pinfunction "GND_A1") (pintype "passive"))
      (node (ref "USB") (pin "A12") (pinfunction "GND_A12") (pintype "passive"))
      (node (ref "USB") (pin "B1") (pinfunction "GND_B1") (pintype "passive"))
      (node (ref "USB") (pin "B12") (pinfunction "GND_B12") (pintype "passive"))
    )
    (net (code "50") (name "Net-(C9-Pad2)") (class "Default")
      (node (ref "C9") (pin "2") (pinfunction "2_2") (pintype "passive"))
      (node (ref "MIC1") (pin "1") (pinfunction "1_1") (pintype "passive"))
      (node (ref "R1") (pin "1") (pinfunction "1_1") (pintype "passive"))
    )
    (net (code "51") (name "Net-(DS3231M-VBAT)") (class "Default")
      (node (ref "BT") (pin "1") (pinfunction "1_1") (pintype "passive"))
      (node (ref "D9") (pin "C") (pinfunction "C_C") (pintype "passive"))
      (node (ref "DS3231M") (pin "6") (pinfunction "VBAT_6") (pintype "passive"))
    )
    (net (code "52") (name "Net-(MT3608-FB)") (class "Default")
      (node (ref "MT3608") (pin "3") (pinfunction "FB_3") (pintype "passive"))
      (node (ref "RB") (pin "2") (pinfunction "2_2") (pintype "passive"))
      (node (ref "RS") (pin "2") (pinfunction "2_2") (pintype "passive"))
    )
    (net (code "53") (name "Net-(MT3608-SW)") (class "Default")
      (node (ref "D3") (pin "A") (pinfunction "A_A") (pintype "passive"))
      (node (ref "L2") (pin "1") (pinfunction "1_1") (pintype "passive"))
      (node (ref "MT3608") (pin "1") (pinfunction "SW_1") (pintype "passive"))
    )
    (net (code "54") (name "Net-(OLED-Pad5)") (class "Default")
      (node (ref "OLED") (pin "5") (pinfunction "5_5") (pintype "passive"))
      (node (ref "R3") (pin "2") (pinfunction "2_2") (pintype "passive"))
    )
    (net (code "55") (name "Net-(OLED-Pad6)") (class "Default")
      (node (ref "OLED") (pin "6") (pinfunction "6_6") (pintype "passive"))
      (node (ref "R2") (pin "2") (pinfunction "2_2") (pintype "passive"))
    )
    (net (code "56") (name "Net-(OLED-Pad7)") (class "Default")
      (node (ref "OLED") (pin "7") (pinfunction "7_7") (pintype "passive"))
      (node (ref "R2") (pin "1") (pinfunction "1_1") (pintype "passive"))
    )
    (net (code "57") (name "Net-(PW-K)") (class "Default")
      (node (ref "PW") (pin "2") (pinfunction "K_2") (pintype "passive"))
      (node (ref "R4") (pin "2") (pinfunction "2_2") (pintype "passive"))
    )
    (net (code "58") (name "Net-(RT9193-BP)") (class "Default")
      (node (ref "C4") (pin "2") (pinfunction "2_2") (pintype "passive"))
      (node (ref "RT9193") (pin "4") (pinfunction "BP_4") (pintype "passive"))
    )
    (net (code "59") (name "Net-(SYS-K)") (class "Default")
      (node (ref "R7") (pin "2") (pinfunction "2_2") (pintype "passive"))
      (node (ref "SYS") (pin "2") (pinfunction "K_2") (pintype "passive"))
    )
    (net (code "60") (name "Net-(U2-BIAS)") (class "Default")
      (node (ref "C10") (pin "1") (pinfunction "1_1") (pintype "passive"))
      (node (ref "U2") (pin "12") (pinfunction "BIAS_12") (pintype "passive"))
    )
    (net (code "61") (name "Net-(U2-CG)") (class "Default")
      (node (ref "C8") (pin "2") (pinfunction "2_2") (pintype "passive"))
      (node (ref "U2") (pin "3") (pinfunction "CG_3") (pintype "passive"))
    )
    (net (code "62") (name "Net-(U2-CT)") (class "Default")
      (node (ref "C6") (pin "2") (pinfunction "2_2") (pintype "passive"))
      (node (ref "U2") (pin "1") (pinfunction "CT_1") (pintype "passive"))
    )
    (net (code "63") (name "Net-(U2-MICBIAS)") (class "Default")
      (node (ref "R1") (pin "2") (pinfunction "2_2") (pintype "passive"))
      (node (ref "R6") (pin "1") (pinfunction "1_1") (pintype "passive"))
      (node (ref "U2") (pin "13") (pinfunction "MICBIAS_13") (pintype "passive"))
    )
    (net (code "64") (name "Net-(U2-MICIN)") (class "Default")
      (node (ref "C9") (pin "1") (pinfunction "1_1") (pintype "passive"))
      (node (ref "U2") (pin "8") (pinfunction "MICIN_8") (pintype "passive"))
    )
    (net (code "65") (name "Net-(U2-TH)") (class "Default")
      (node (ref "R6") (pin "2") (pinfunction "2_2") (pintype "passive"))
      (node (ref "R8") (pin "2") (pinfunction "2_2") (pintype "passive"))
      (node (ref "U2") (pin "14") (pinfunction "TH_14") (pintype "passive"))
    )
    (net (code "66") (name "Net-(U3-AD0)") (class "Default")
      (node (ref "R9") (pin "2") (pinfunction "2_2") (pintype "passive"))
      (node (ref "U3") (pin "9") (pinfunction "AD0_9") (pintype "passive"))
    )
    (net (code "67") (name "Net-(U3-CPOUT)") (class "Default")
      (node (ref "C23") (pin "2") (pinfunction "2_2") (pintype "passive"))
      (node (ref "U3") (pin "20") (pinfunction "CPOUT_20") (pintype "passive"))
    )
    (net (code "68") (name "Net-(U3-REGOUT)") (class "Default")
      (node (ref "C24") (pin "2") (pinfunction "2_2") (pintype "passive"))
      (node (ref "U3") (pin "10") (pinfunction "REGOUT_10") (pintype "passive"))
    )
    (net (code "69") (name "Net-(U4-PROG)") (class "Default")
      (node (ref "R13") (pin "1") (pinfunction "1_1") (pintype "passive"))
      (node (ref "U4") (pin "6") (pinfunction "PROG_6") (pintype "passive"))
    )
    (net (code "70") (name "OLEDVPP") (class "Default")
      (node (ref "C11") (pin "1") (pinfunction "1_1") (pintype "passive"))
      (node (ref "C12") (pin "1") (pinfunction "1_1") (pintype "passive"))
      (node (ref "C7") (pin "1") (pinfunction "1_1") (pintype "passive"))
      (node (ref "D3") (pin "C") (pinfunction "C_C") (pintype "passive"))
      (node (ref "OLED") (pin "3") (pinfunction "3_3") (pintype "passive"))
      (node (ref "OLED") (pin "33") (pinfunction "33_33") (pintype "passive"))
      (node (ref "RB") (pin "1") (pinfunction "1_1") (pintype "passive"))
    )
    (net (code "71") (name "unconnected-(CH340E-CTS#-Pad5)") (class "Default")
      (node (ref "CH340E") (pin "5") (pinfunction "CTS#_5") (pintype "passive"))
    )
    (net (code "72") (name "unconnected-(CH340E-RTS#-Pad4)") (class "Default")
      (node (ref "CH340E") (pin "4") (pinfunction "RTS#_4") (pintype "passive"))
    )
    (net (code "73") (name "unconnected-(CH340E-TNOW-Pad6)") (class "Default")
      (node (ref "CH340E") (pin "6") (pinfunction "TNOW_6") (pintype "passive"))
    )
    (net (code "74") (name "unconnected-(DS3231M-32kHZ-Pad1)") (class "Default")
      (node (ref "DS3231M") (pin "1") (pinfunction "32kHZ_1") (pintype "passive"))
    )
    (net (code "75") (name "unconnected-(DS3231M-RST-Pad4)") (class "Default")
      (node (ref "DS3231M") (pin "4") (pinfunction "RST_4") (pintype "passive"))
    )
    (net (code "76") (name "unconnected-(MT3608-NC-Pad6)") (class "Default")
      (node (ref "MT3608") (pin "6") (pinfunction "NC_6") (pintype "passive"))
    )
    (net (code "77") (name "unconnected-(OLED-Pad1)") (class "Default")
      (node (ref "OLED") (pin "1") (pinfunction "1_1") (pintype "passive+no_connect"))
    )
    (net (code "78") (name "unconnected-(OLED-Pad9)") (class "Default")
      (node (ref "OLED") (pin "9") (pinfunction "9_9") (pintype "passive+no_connect"))
    )
    (net (code "79") (name "unconnected-(OLED-Pad10)") (class "Default")
      (node (ref "OLED") (pin "10") (pinfunction "10_10") (pintype "passive"))
    )
    (net (code "80") (name "unconnected-(OLED-Pad11)") (class "Default")
      (node (ref "OLED") (pin "11") (pinfunction "11_11") (pintype "passive"))
    )
    (net (code "81") (name "unconnected-(OLED-Pad12)") (class "Default")
      (node (ref "OLED") (pin "12") (pinfunction "12_12") (pintype "passive"))
    )
    (net (code "82") (name "unconnected-(OLED-Pad13)") (class "Default")
      (node (ref "OLED") (pin "13") (pinfunction "13_13") (pintype "passive"))
    )
    (net (code "83") (name "unconnected-(OLED-Pad35)") (class "Default")
      (node (ref "OLED") (pin "35") (pinfunction "35_35") (pintype "passive+no_connect"))
    )
    (net (code "84") (name "unconnected-(U3-EP-Pad25)") (class "Default")
      (node (ref "U3") (pin "25") (pinfunction "EP_25") (pintype "passive+no_connect"))
    )
    (net (code "85") (name "unconnected-(U3-NC-Pad2)") (class "Default")
      (node (ref "U3") (pin "2") (pinfunction "NC_2") (pintype "passive+no_connect"))
    )
    (net (code "86") (name "unconnected-(U3-NC-Pad3)") (class "Default")
      (node (ref "U3") (pin "3") (pinfunction "NC_3") (pintype "passive+no_connect"))
    )
    (net (code "87") (name "unconnected-(U3-NC-Pad4)") (class "Default")
      (node (ref "U3") (pin "4") (pinfunction "NC_4") (pintype "passive+no_connect"))
    )
    (net (code "88") (name "unconnected-(U3-NC-Pad5)") (class "Default")
      (node (ref "U3") (pin "5") (pinfunction "NC_5") (pintype "passive+no_connect"))
    )
    (net (code "89") (name "unconnected-(U3-NC-Pad14)") (class "Default")
      (node (ref "U3") (pin "14") (pinfunction "NC_14") (pintype "passive+no_connect"))
    )
    (net (code "90") (name "unconnected-(U3-NC-Pad15)") (class "Default")
      (node (ref "U3") (pin "15") (pinfunction "NC_15") (pintype "passive+no_connect"))
    )
    (net (code "91") (name "unconnected-(U3-NC-Pad16)") (class "Default")
      (node (ref "U3") (pin "16") (pinfunction "NC_16") (pintype "passive+no_connect"))
    )
    (net (code "92") (name "unconnected-(U3-NC-Pad17)") (class "Default")
      (node (ref "U3") (pin "17") (pinfunction "NC_17") (pintype "passive+no_connect"))
    )
    (net (code "93") (name "unconnected-(U3-RESV-Pad19)") (class "Default")
      (node (ref "U3") (pin "19") (pinfunction "RESV_19") (pintype "passive+no_connect"))
    )
    (net (code "94") (name "unconnected-(U3-RESV-Pad21)") (class "Default")
      (node (ref "U3") (pin "21") (pinfunction "RESV_21") (pintype "passive+no_connect"))
    )
    (net (code "95") (name "unconnected-(U3-RESV-Pad22)") (class "Default")
      (node (ref "U3") (pin "22") (pinfunction "RESV_22") (pintype "passive+no_connect"))
    )
    (net (code "96") (name "unconnected-(U4-STDBY-Pad5)") (class "Default")
      (node (ref "U4") (pin "5") (pinfunction "STDBY_5") (pintype "passive"))
    )
    (net (code "97") (name "unconnected-(USB-CC1-PadA5)") (class "Default")
      (node (ref "USB") (pin "A5") (pinfunction "CC1_A5") (pintype "passive"))
    )
    (net (code "98") (name "unconnected-(USB-CC2-PadB5)") (class "Default")
      (node (ref "USB") (pin "B5") (pinfunction "CC2_B5") (pintype "passive+no_connect"))
    )
    (net (code "99") (name "unconnected-(USB-RX1+-PadB11)") (class "Default")
      (node (ref "USB") (pin "B11") (pinfunction "RX1+_B11") (pintype "passive+no_connect"))
    )
    (net (code "100") (name "unconnected-(USB-RX1--PadB10)") (class "Default")
      (node (ref "USB") (pin "B10") (pinfunction "RX1-_B10") (pintype "passive+no_connect"))
    )
    (net (code "101") (name "unconnected-(USB-RX2+-PadA11)") (class "Default")
      (node (ref "USB") (pin "A11") (pinfunction "RX2+_A11") (pintype "passive+no_connect"))
    )
    (net (code "102") (name "unconnected-(USB-RX2--PadA10)") (class "Default")
      (node (ref "USB") (pin "A10") (pinfunction "RX2-_A10") (pintype "passive+no_connect"))
    )
    (net (code "103") (name "unconnected-(USB-SBU1-PadA8)") (class "Default")
      (node (ref "USB") (pin "A8") (pinfunction "SBU1_A8") (pintype "passive+no_connect"))
    )
    (net (code "104") (name "unconnected-(USB-SBU2-PadB8)") (class "Default")
      (node (ref "USB") (pin "B8") (pinfunction "SBU2_B8") (pintype "passive"))
    )
    (net (code "105") (name "unconnected-(USB-TX1+-PadA2)") (class "Default")
      (node (ref "USB") (pin "A2") (pinfunction "TX1+_A2") (pintype "passive+no_connect"))
    )
    (net (code "106") (name "unconnected-(USB-TX1--PadA3)") (class "Default")
      (node (ref "USB") (pin "A3") (pinfunction "TX1-_A3") (pintype "passive+no_connect"))
    )
    (net (code "107") (name "unconnected-(USB-TX2+-PadB2)") (class "Default")
      (node (ref "USB") (pin "B2") (pinfunction "TX2+_B2") (pintype "passive+no_connect"))
    )
    (net (code "108") (name "unconnected-(USB-TX2--PadB3)") (class "Default")
      (node (ref "USB") (pin "B3") (pinfunction "TX2-_B3") (pintype "passive+no_connect"))
    )
  )
)
